# heated_bed.net
KiCad netlist of a schematic drawn in EAGLE
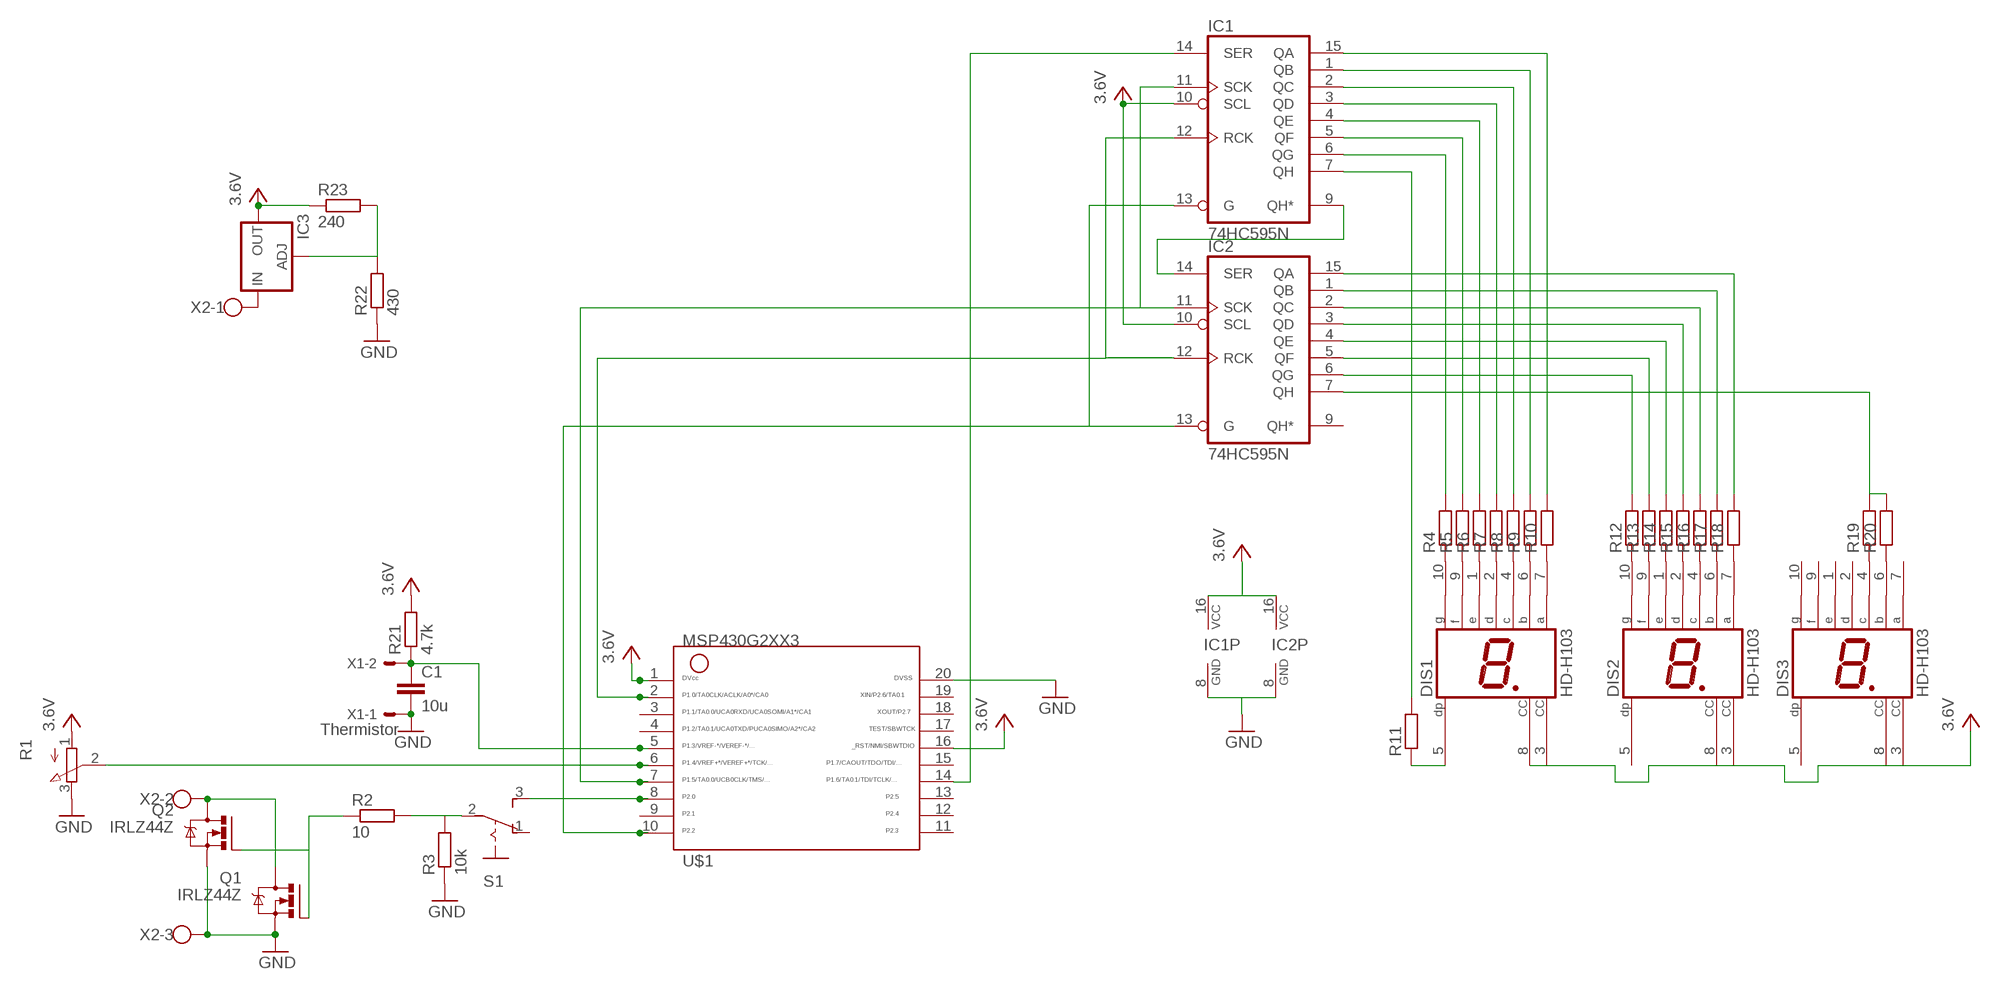
[diagram p0: schematic, sheet 1]

(export (version "E")
  (design (tool "Eeschema 10.0.6"))
  (components
    (comp (ref "C1")
      (value "10u")
      (footprint "eagle-import:C025-050X050")
      (libsource (lib "eagle-import") (part "C-EU025-050X050"))
    )
    (comp (ref "DIS1")
      (value "HD-H103")
      (footprint "eagle-import:HDSP-M")
      (libsource (lib "eagle-import") (part "HD-H103"))
    )
    (comp (ref "DIS2")
      (value "HD-H103")
      (footprint "eagle-import:HDSP-M")
      (libsource (lib "eagle-import") (part "HD-H103"))
    )
    (comp (ref "DIS3")
      (value "HD-H103")
      (footprint "eagle-import:HDSP-M")
      (libsource (lib "eagle-import") (part "HD-H103"))
    )
    (comp (ref "IC1")
      (value "74HC595N")
      (footprint "eagle-import:DIL16")
      (libsource (lib "eagle-import") (part "74595NHC"))
    )
    (comp (ref "IC2")
      (value "74HC595N")
      (footprint "eagle-import:DIL16")
      (libsource (lib "eagle-import") (part "74595NHC"))
    )
    (comp (ref "IC3")
      (value "LM317L")
      (footprint "eagle-import:317L")
      (libsource (lib "eagle-import") (part "LM317L"))
    )
    (comp (ref "Q1")
      (value "IRLZ44Z")
      (footprint "eagle-import:TO220BH")
      (libsource (lib "eagle-import") (part "IRLZ44Z"))
    )
    (comp (ref "Q2")
      (value "IRLZ44Z")
      (footprint "eagle-import:TO220BH")
      (libsource (lib "eagle-import") (part "IRLZ44Z"))
    )
    (comp (ref "R1")
      (value "3RP/1610N")
      (footprint "eagle-import:3RP_1610N")
      (libsource (lib "eagle-import") (part "3RP/1610N"))
    )
    (comp (ref "R2")
      (value "10")
      (footprint "eagle-import:0207_2V")
      (libsource (lib "eagle-import") (part "R-EU_0207/2V"))
    )
    (comp (ref "R3")
      (value "10k")
      (footprint "eagle-import:0207_2V")
      (libsource (lib "eagle-import") (part "R-EU_0207/2V"))
    )
    (comp (ref "R4")
      (value "R-EU_0207/2V")
      (footprint "eagle-import:0207_2V")
      (libsource (lib "eagle-import") (part "R-EU_0207/2V"))
    )
    (comp (ref "R5")
      (value "R-EU_0207/2V")
      (footprint "eagle-import:0207_2V")
      (libsource (lib "eagle-import") (part "R-EU_0207/2V"))
    )
    (comp (ref "R6")
      (value "R-EU_0207/2V")
      (footprint "eagle-import:0207_2V")
      (libsource (lib "eagle-import") (part "R-EU_0207/2V"))
    )
    (comp (ref "R7")
      (value "R-EU_0207/2V")
      (footprint "eagle-import:0207_2V")
      (libsource (lib "eagle-import") (part "R-EU_0207/2V"))
    )
    (comp (ref "R8")
      (value "R-EU_0207/2V")
      (footprint "eagle-import:0207_2V")
      (libsource (lib "eagle-import") (part "R-EU_0207/2V"))
    )
    (comp (ref "R9")
      (value "R-EU_0207/2V")
      (footprint "eagle-import:0207_2V")
      (libsource (lib "eagle-import") (part "R-EU_0207/2V"))
    )
    (comp (ref "R10")
      (value "R-EU_0207/2V")
      (footprint "eagle-import:0207_2V")
      (libsource (lib "eagle-import") (part "R-EU_0207/2V"))
    )
    (comp (ref "R11")
      (value "R-EU_0207/2V")
      (footprint "eagle-import:0207_2V")
      (libsource (lib "eagle-import") (part "R-EU_0207/2V"))
    )
    (comp (ref "R12")
      (value "R-EU_0207/2V")
      (footprint "eagle-import:0207_2V")
      (libsource (lib "eagle-import") (part "R-EU_0207/2V"))
    )
    (comp (ref "R13")
      (value "R-EU_0207/2V")
      (footprint "eagle-import:0207_2V")
      (libsource (lib "eagle-import") (part "R-EU_0207/2V"))
    )
    (comp (ref "R14")
      (value "R-EU_0207/2V")
      (footprint "eagle-import:0207_2V")
      (libsource (lib "eagle-import") (part "R-EU_0207/2V"))
    )
    (comp (ref "R15")
      (value "R-EU_0207/2V")
      (footprint "eagle-import:0207_2V")
      (libsource (lib "eagle-import") (part "R-EU_0207/2V"))
    )
    (comp (ref "R16")
      (value "R-EU_0207/2V")
      (footprint "eagle-import:0207_2V")
      (libsource (lib "eagle-import") (part "R-EU_0207/2V"))
    )
    (comp (ref "R17")
      (value "R-EU_0207/2V")
      (footprint "eagle-import:0207_2V")
      (libsource (lib "eagle-import") (part "R-EU_0207/2V"))
    )
    (comp (ref "R18")
      (value "R-EU_0207/2V")
      (footprint "eagle-import:0207_2V")
      (libsource (lib "eagle-import") (part "R-EU_0207/2V"))
    )
    (comp (ref "R19")
      (value "R-EU_0207/2V")
      (footprint "eagle-import:0207_2V")
      (libsource (lib "eagle-import") (part "R-EU_0207/2V"))
    )
    (comp (ref "R20")
      (value "R-EU_0207/2V")
      (footprint "eagle-import:0207_2V")
      (libsource (lib "eagle-import") (part "R-EU_0207/2V"))
    )
    (comp (ref "R21")
      (value "4.7k")
      (footprint "eagle-import:0207_2V")
      (libsource (lib "eagle-import") (part "R-EU_0207/2V"))
    )
    (comp (ref "R22")
      (value "430")
      (footprint "eagle-import:0207_2V")
      (libsource (lib "eagle-import") (part "R-EU_0207/2V"))
    )
    (comp (ref "R23")
      (value "240")
      (footprint "eagle-import:0207_2V")
      (libsource (lib "eagle-import") (part "R-EU_0207/2V"))
    )
    (comp (ref "S1")
      (value "255SB")
      (footprint "eagle-import:255SB")
      (libsource (lib "eagle-import") (part "255SB"))
    )
    (comp (ref "U$1")
      (value "G2XX3---N20")
      (footprint "eagle-import:N20")
      (libsource (lib "eagle-import") (part "G2XX3---N20"))
    )
    (comp (ref "X1")
      (value "Thermistor")
      (footprint "eagle-import:22-23-2021")
      (fields (field (name "MF") "MOLEX") (field (name "MPN") "22-23-2021"))
      (libsource (lib "eagle-import") (part "22-23-2021"))
    )
    (comp (ref "X2")
      (value "W237-103")
      (footprint "eagle-import:W237-103")
      (fields (field (name "MPN") "237-103"))
      (libsource (lib "eagle-import") (part "W237-103"))
    )
  )
  (nets
    (net (code "1") (name "3.6V") (class "Default")
      (node (ref "DIS1") (pin "3") (pinfunction "CC_3") (pintype "passive"))
      (node (ref "DIS1") (pin "8") (pinfunction "CC_8") (pintype "passive"))
      (node (ref "DIS2") (pin "3") (pinfunction "CC_3") (pintype "passive"))
      (node (ref "DIS2") (pin "8") (pinfunction "CC_8") (pintype "passive"))
      (node (ref "DIS3") (pin "3") (pinfunction "CC_3") (pintype "passive"))
      (node (ref "DIS3") (pin "8") (pinfunction "CC_8") (pintype "passive"))
      (node (ref "IC1") (pin "10") (pinfunction "SCL_10") (pintype "input"))
      (node (ref "IC1") (pin "16") (pinfunction "VCC_16") (pintype "power_in"))
      (node (ref "IC2") (pin "10") (pinfunction "SCL_10") (pintype "input"))
      (node (ref "IC2") (pin "16") (pinfunction "VCC_16") (pintype "power_in"))
      (node (ref "IC3") (pin "2") (pinfunction "OUT_2") (pintype "passive"))
      (node (ref "R1") (pin "1") (pinfunction "A_1") (pintype "passive"))
      (node (ref "R21") (pin "2") (pinfunction "2_2") (pintype "passive"))
      (node (ref "R23") (pin "1") (pinfunction "1_1") (pintype "passive"))
      (node (ref "U$1") (pin "1") (pinfunction "1_1") (pintype "bidirectional"))
      (node (ref "U$1") (pin "16") (pinfunction "16_16") (pintype "bidirectional"))
    )
    (net (code "2") (name "GND") (class "Default")
      (node (ref "C1") (pin "2") (pinfunction "2_2") (pintype "passive"))
      (node (ref "IC1") (pin "8") (pinfunction "GND_8") (pintype "power_in"))
      (node (ref "IC2") (pin "8") (pinfunction "GND_8") (pintype "power_in"))
      (node (ref "Q1") (pin "S") (pinfunction "S_S") (pintype "passive"))
      (node (ref "Q2") (pin "S") (pinfunction "S_S") (pintype "passive"))
      (node (ref "R1") (pin "3") (pinfunction "E_3") (pintype "passive"))
      (node (ref "R22") (pin "1") (pinfunction "1_1") (pintype "passive"))
      (node (ref "R3") (pin "1") (pinfunction "1_1") (pintype "passive"))
      (node (ref "U$1") (pin "20") (pinfunction "20_20") (pintype "bidirectional"))
      (node (ref "X1") (pin "1") (pinfunction "S_1") (pintype "passive"))
      (node (ref "X2") (pin "3") (pinfunction "KL_3") (pintype "passive"))
    )
    (net (code "3") (name "Net-(DIS1-A)") (class "Default")
      (node (ref "DIS1") (pin "7") (pinfunction "A_7") (pintype "passive"))
      (node (ref "R10") (pin "1") (pinfunction "1_1") (pintype "passive"))
    )
    (net (code "4") (name "Net-(DIS1-B)") (class "Default")
      (node (ref "DIS1") (pin "6") (pinfunction "B_6") (pintype "passive"))
      (node (ref "R9") (pin "1") (pinfunction "1_1") (pintype "passive"))
    )
    (net (code "5") (name "Net-(DIS1-C)") (class "Default")
      (node (ref "DIS1") (pin "4") (pinfunction "C_4") (pintype "passive"))
      (node (ref "R8") (pin "1") (pinfunction "1_1") (pintype "passive"))
    )
    (net (code "6") (name "Net-(DIS1-D)") (class "Default")
      (node (ref "DIS1") (pin "2") (pinfunction "D_2") (pintype "passive"))
      (node (ref "R7") (pin "1") (pinfunction "1_1") (pintype "passive"))
    )
    (net (code "7") (name "Net-(DIS1-DP)") (class "Default")
      (node (ref "DIS1") (pin "5") (pinfunction "DP_5") (pintype "passive"))
      (node (ref "R11") (pin "1") (pinfunction "1_1") (pintype "passive"))
    )
    (net (code "8") (name "Net-(DIS1-E)") (class "Default")
      (node (ref "DIS1") (pin "1") (pinfunction "E_1") (pintype "passive"))
      (node (ref "R6") (pin "1") (pinfunction "1_1") (pintype "passive"))
    )
    (net (code "9") (name "Net-(DIS1-F)") (class "Default")
      (node (ref "DIS1") (pin "9") (pinfunction "F_9") (pintype "passive"))
      (node (ref "R5") (pin "1") (pinfunction "1_1") (pintype "passive"))
    )
    (net (code "10") (name "Net-(DIS1-G)") (class "Default")
      (node (ref "DIS1") (pin "10") (pinfunction "G_10") (pintype "passive"))
      (node (ref "R4") (pin "1") (pinfunction "1_1") (pintype "passive"))
    )
    (net (code "11") (name "Net-(DIS2-A)") (class "Default")
      (node (ref "DIS2") (pin "7") (pinfunction "A_7") (pintype "passive"))
      (node (ref "R18") (pin "1") (pinfunction "1_1") (pintype "passive"))
    )
    (net (code "12") (name "Net-(DIS2-B)") (class "Default")
      (node (ref "DIS2") (pin "6") (pinfunction "B_6") (pintype "passive"))
      (node (ref "R17") (pin "1") (pinfunction "1_1") (pintype "passive"))
    )
    (net (code "13") (name "Net-(DIS2-C)") (class "Default")
      (node (ref "DIS2") (pin "4") (pinfunction "C_4") (pintype "passive"))
      (node (ref "R16") (pin "1") (pinfunction "1_1") (pintype "passive"))
    )
    (net (code "14") (name "Net-(DIS2-D)") (class "Default")
      (node (ref "DIS2") (pin "2") (pinfunction "D_2") (pintype "passive"))
      (node (ref "R15") (pin "1") (pinfunction "1_1") (pintype "passive"))
    )
    (net (code "15") (name "Net-(DIS2-E)") (class "Default")
      (node (ref "DIS2") (pin "1") (pinfunction "E_1") (pintype "passive"))
      (node (ref "R14") (pin "1") (pinfunction "1_1") (pintype "passive"))
    )
    (net (code "16") (name "Net-(DIS2-F)") (class "Default")
      (node (ref "DIS2") (pin "9") (pinfunction "F_9") (pintype "passive"))
      (node (ref "R13") (pin "1") (pinfunction "1_1") (pintype "passive"))
    )
    (net (code "17") (name "Net-(DIS2-G)") (class "Default")
      (node (ref "DIS2") (pin "10") (pinfunction "G_10") (pintype "passive"))
      (node (ref "R12") (pin "1") (pinfunction "1_1") (pintype "passive"))
    )
    (net (code "18") (name "Net-(DIS3-B)") (class "Default")
      (node (ref "DIS3") (pin "6") (pinfunction "B_6") (pintype "passive"))
      (node (ref "R20") (pin "1") (pinfunction "1_1") (pintype "passive"))
    )
    (net (code "19") (name "Net-(DIS3-C)") (class "Default")
      (node (ref "DIS3") (pin "4") (pinfunction "C_4") (pintype "passive"))
      (node (ref "R19") (pin "1") (pinfunction "1_1") (pintype "passive"))
    )
    (net (code "20") (name "Net-(IC1A-G)") (class "Default")
      (node (ref "IC1") (pin "13") (pinfunction "G_13") (pintype "input"))
      (node (ref "IC2") (pin "13") (pinfunction "G_13") (pintype "input"))
      (node (ref "U$1") (pin "10") (pinfunction "10_10") (pintype "bidirectional"))
    )
    (net (code "21") (name "Net-(IC1A-QA)") (class "Default")
      (node (ref "IC1") (pin "15") (pinfunction "QA_15") (pintype "tri_state"))
      (node (ref "R10") (pin "2") (pinfunction "2_2") (pintype "passive"))
    )
    (net (code "22") (name "Net-(IC1A-QB)") (class "Default")
      (node (ref "IC1") (pin "1") (pinfunction "QB_1") (pintype "tri_state"))
      (node (ref "R9") (pin "2") (pinfunction "2_2") (pintype "passive"))
    )
    (net (code "23") (name "Net-(IC1A-QC)") (class "Default")
      (node (ref "IC1") (pin "2") (pinfunction "QC_2") (pintype "tri_state"))
      (node (ref "R8") (pin "2") (pinfunction "2_2") (pintype "passive"))
    )
    (net (code "24") (name "Net-(IC1A-QD)") (class "Default")
      (node (ref "IC1") (pin "3") (pinfunction "QD_3") (pintype "tri_state"))
      (node (ref "R7") (pin "2") (pinfunction "2_2") (pintype "passive"))
    )
    (net (code "25") (name "Net-(IC1A-QE)") (class "Default")
      (node (ref "IC1") (pin "4") (pinfunction "QE_4") (pintype "tri_state"))
      (node (ref "R6") (pin "2") (pinfunction "2_2") (pintype "passive"))
    )
    (net (code "26") (name "Net-(IC1A-QF)") (class "Default")
      (node (ref "IC1") (pin "5") (pinfunction "QF_5") (pintype "tri_state"))
      (node (ref "R5") (pin "2") (pinfunction "2_2") (pintype "passive"))
    )
    (net (code "27") (name "Net-(IC1A-QG)") (class "Default")
      (node (ref "IC1") (pin "6") (pinfunction "QG_6") (pintype "tri_state"))
      (node (ref "R4") (pin "2") (pinfunction "2_2") (pintype "passive"))
    )
    (net (code "28") (name "Net-(IC1A-QH)") (class "Default")
      (node (ref "IC1") (pin "7") (pinfunction "QH_7") (pintype "tri_state"))
      (node (ref "R11") (pin "2") (pinfunction "2_2") (pintype "passive"))
    )
    (net (code "29") (name "Net-(IC1A-QH*)") (class "Default")
      (node (ref "IC1") (pin "9") (pinfunction "QH*_9") (pintype "tri_state"))
      (node (ref "IC2") (pin "14") (pinfunction "SER_14") (pintype "input"))
    )
    (net (code "30") (name "Net-(IC1A-RCK)") (class "Default")
      (node (ref "IC1") (pin "12") (pinfunction "RCK_12") (pintype "input"))
      (node (ref "IC2") (pin "12") (pinfunction "RCK_12") (pintype "input"))
      (node (ref "U$1") (pin "2") (pinfunction "2_2") (pintype "bidirectional"))
    )
    (net (code "31") (name "Net-(IC1A-SCK)") (class "Default")
      (node (ref "IC1") (pin "11") (pinfunction "SCK_11") (pintype "input"))
      (node (ref "IC2") (pin "11") (pinfunction "SCK_11") (pintype "input"))
      (node (ref "U$1") (pin "7") (pinfunction "7_7") (pintype "bidirectional"))
    )
    (net (code "32") (name "Net-(IC1A-SER)") (class "Default")
      (node (ref "IC1") (pin "14") (pinfunction "SER_14") (pintype "input"))
      (node (ref "U$1") (pin "14") (pinfunction "14_14") (pintype "bidirectional"))
    )
    (net (code "33") (name "Net-(IC2A-QA)") (class "Default")
      (node (ref "IC2") (pin "15") (pinfunction "QA_15") (pintype "tri_state"))
      (node (ref "R18") (pin "2") (pinfunction "2_2") (pintype "passive"))
    )
    (net (code "34") (name "Net-(IC2A-QB)") (class "Default")
      (node (ref "IC2") (pin "1") (pinfunction "QB_1") (pintype "tri_state"))
      (node (ref "R17") (pin "2") (pinfunction "2_2") (pintype "passive"))
    )
    (net (code "35") (name "Net-(IC2A-QC)") (class "Default")
      (node (ref "IC2") (pin "2") (pinfunction "QC_2") (pintype "tri_state"))
      (node (ref "R16") (pin "2") (pinfunction "2_2") (pintype "passive"))
    )
    (net (code "36") (name "Net-(IC2A-QD)") (class "Default")
      (node (ref "IC2") (pin "3") (pinfunction "QD_3") (pintype "tri_state"))
      (node (ref "R15") (pin "2") (pinfunction "2_2") (pintype "passive"))
    )
    (net (code "37") (name "Net-(IC2A-QE)") (class "Default")
      (node (ref "IC2") (pin "4") (pinfunction "QE_4") (pintype "tri_state"))
      (node (ref "R14") (pin "2") (pinfunction "2_2") (pintype "passive"))
    )
    (net (code "38") (name "Net-(IC2A-QF)") (class "Default")
      (node (ref "IC2") (pin "5") (pinfunction "QF_5") (pintype "tri_state"))
      (node (ref "R13") (pin "2") (pinfunction "2_2") (pintype "passive"))
    )
    (net (code "39") (name "Net-(IC2A-QG)") (class "Default")
      (node (ref "IC2") (pin "6") (pinfunction "QG_6") (pintype "tri_state"))
      (node (ref "R12") (pin "2") (pinfunction "2_2") (pintype "passive"))
    )
    (net (code "40") (name "Net-(IC2A-QH)") (class "Default")
      (node (ref "IC2") (pin "7") (pinfunction "QH_7") (pintype "tri_state"))
      (node (ref "R19") (pin "2") (pinfunction "2_2") (pintype "passive"))
      (node (ref "R20") (pin "2") (pinfunction "2_2") (pintype "passive"))
    )
    (net (code "41") (name "Net-(IC3-ADJ)") (class "Default")
      (node (ref "IC3") (pin "1") (pinfunction "ADJ_1") (pintype "input"))
      (node (ref "R22") (pin "2") (pinfunction "2_2") (pintype "passive"))
      (node (ref "R23") (pin "2") (pinfunction "2_2") (pintype "passive"))
    )
    (net (code "42") (name "Net-(IC3-IN)") (class "Default")
      (node (ref "IC3") (pin "3") (pinfunction "IN_3") (pintype "input"))
      (node (ref "X2") (pin "1") (pinfunction "KL_1") (pintype "passive"))
    )
    (net (code "43") (name "Net-(Q1-PadG)") (class "Default")
      (node (ref "Q1") (pin "G") (pinfunction "G_G") (pintype "passive"))
      (node (ref "Q2") (pin "G") (pinfunction "G_G") (pintype "passive"))
      (node (ref "R2") (pin "1") (pinfunction "1_1") (pintype "passive"))
    )
    (net (code "44") (name "Net-(R1-S)") (class "Default")
      (node (ref "R1") (pin "2") (pinfunction "S_2") (pintype "passive"))
      (node (ref "U$1") (pin "6") (pinfunction "6_6") (pintype "bidirectional"))
    )
    (net (code "45") (name "Net-(S1-P)") (class "Default")
      (node (ref "R2") (pin "2") (pinfunction "2_2") (pintype "passive"))
      (node (ref "R3") (pin "2") (pinfunction "2_2") (pintype "passive"))
      (node (ref "S1") (pin "2") (pinfunction "P_2") (pintype "passive"))
    )
    (net (code "46") (name "Net-(S1-S)") (class "Default")
      (node (ref "S1") (pin "3") (pinfunction "S_3") (pintype "passive"))
      (node (ref "U$1") (pin "8") (pinfunction "8_8") (pintype "bidirectional"))
    )
    (net (code "47") (name "Net-(X1B-S)") (class "Default")
      (node (ref "C1") (pin "1") (pinfunction "1_1") (pintype "passive"))
      (node (ref "R21") (pin "1") (pinfunction "1_1") (pintype "passive"))
      (node (ref "U$1") (pin "5") (pinfunction "5_5") (pintype "bidirectional"))
      (node (ref "X1") (pin "2") (pinfunction "S_2") (pintype "passive"))
    )
    (net (code "48") (name "Net-(X2B-KL)") (class "Default")
      (node (ref "Q1") (pin "D") (pinfunction "D_D") (pintype "passive"))
      (node (ref "Q2") (pin "D") (pinfunction "D_D") (pintype "passive"))
      (node (ref "X2") (pin "2") (pinfunction "KL_2") (pintype "passive"))
    )
    (net (code "49") (name "unconnected-(DIS2-DP-Pad5)") (class "Default")
      (node (ref "DIS2") (pin "5") (pinfunction "DP_5") (pintype "passive"))
    )
    (net (code "50") (name "unconnected-(DIS3-A-Pad7)") (class "Default")
      (node (ref "DIS3") (pin "7") (pinfunction "A_7") (pintype "passive"))
    )
    (net (code "51") (name "unconnected-(DIS3-D-Pad2)") (class "Default")
      (node (ref "DIS3") (pin "2") (pinfunction "D_2") (pintype "passive"))
    )
    (net (code "52") (name "unconnected-(DIS3-DP-Pad5)") (class "Default")
      (node (ref "DIS3") (pin "5") (pinfunction "DP_5") (pintype "passive"))
    )
    (net (code "53") (name "unconnected-(DIS3-E-Pad1)") (class "Default")
      (node (ref "DIS3") (pin "1") (pinfunction "E_1") (pintype "passive"))
    )
    (net (code "54") (name "unconnected-(DIS3-F-Pad9)") (class "Default")
      (node (ref "DIS3") (pin "9") (pinfunction "F_9") (pintype "passive"))
    )
    (net (code "55") (name "unconnected-(DIS3-G-Pad10)") (class "Default")
      (node (ref "DIS3") (pin "10") (pinfunction "G_10") (pintype "passive"))
    )
    (net (code "56") (name "unconnected-(IC2A-QH*-Pad9)") (class "Default")
      (node (ref "IC2") (pin "9") (pinfunction "QH*_9") (pintype "tri_state"))
    )
    (net (code "57") (name "unconnected-(S1-O-Pad1)") (class "Default")
      (node (ref "S1") (pin "1") (pinfunction "O_1") (pintype "passive"))
    )
    (net (code "58") (name "unconnected-(U$1-Pad3)") (class "Default")
      (node (ref "U$1") (pin "3") (pinfunction "3_3") (pintype "bidirectional"))
    )
    (net (code "59") (name "unconnected-(U$1-Pad4)") (class "Default")
      (node (ref "U$1") (pin "4") (pinfunction "4_4") (pintype "bidirectional"))
    )
    (net (code "60") (name "unconnected-(U$1-Pad9)") (class "Default")
      (node (ref "U$1") (pin "9") (pinfunction "9_9") (pintype "bidirectional"))
    )
    (net (code "61") (name "unconnected-(U$1-Pad11)") (class "Default")
      (node (ref "U$1") (pin "11") (pinfunction "11_11") (pintype "bidirectional"))
    )
    (net (code "62") (name "unconnected-(U$1-Pad12)") (class "Default")
      (node (ref "U$1") (pin "12") (pinfunction "12_12") (pintype "bidirectional"))
    )
    (net (code "63") (name "unconnected-(U$1-Pad13)") (class "Default")
      (node (ref "U$1") (pin "13") (pinfunction "13_13") (pintype "bidirectional"))
    )
    (net (code "64") (name "unconnected-(U$1-Pad15)") (class "Default")
      (node (ref "U$1") (pin "15") (pinfunction "15_15") (pintype "bidirectional"))
    )
    (net (code "65") (name "unconnected-(U$1-Pad17)") (class "Default")
      (node (ref "U$1") (pin "17") (pinfunction "17_17") (pintype "bidirectional"))
    )
    (net (code "66") (name "unconnected-(U$1-Pad18)") (class "Default")
      (node (ref "U$1") (pin "18") (pinfunction "18_18") (pintype "bidirectional"))
    )
    (net (code "67") (name "unconnected-(U$1-Pad19)") (class "Default")
      (node (ref "U$1") (pin "19") (pinfunction "19_19") (pintype "bidirectional"))
    )
  )
)
